# Snyder1_ESP32_V5.net
KiCad netlist of a schematic drawn in EAGLE
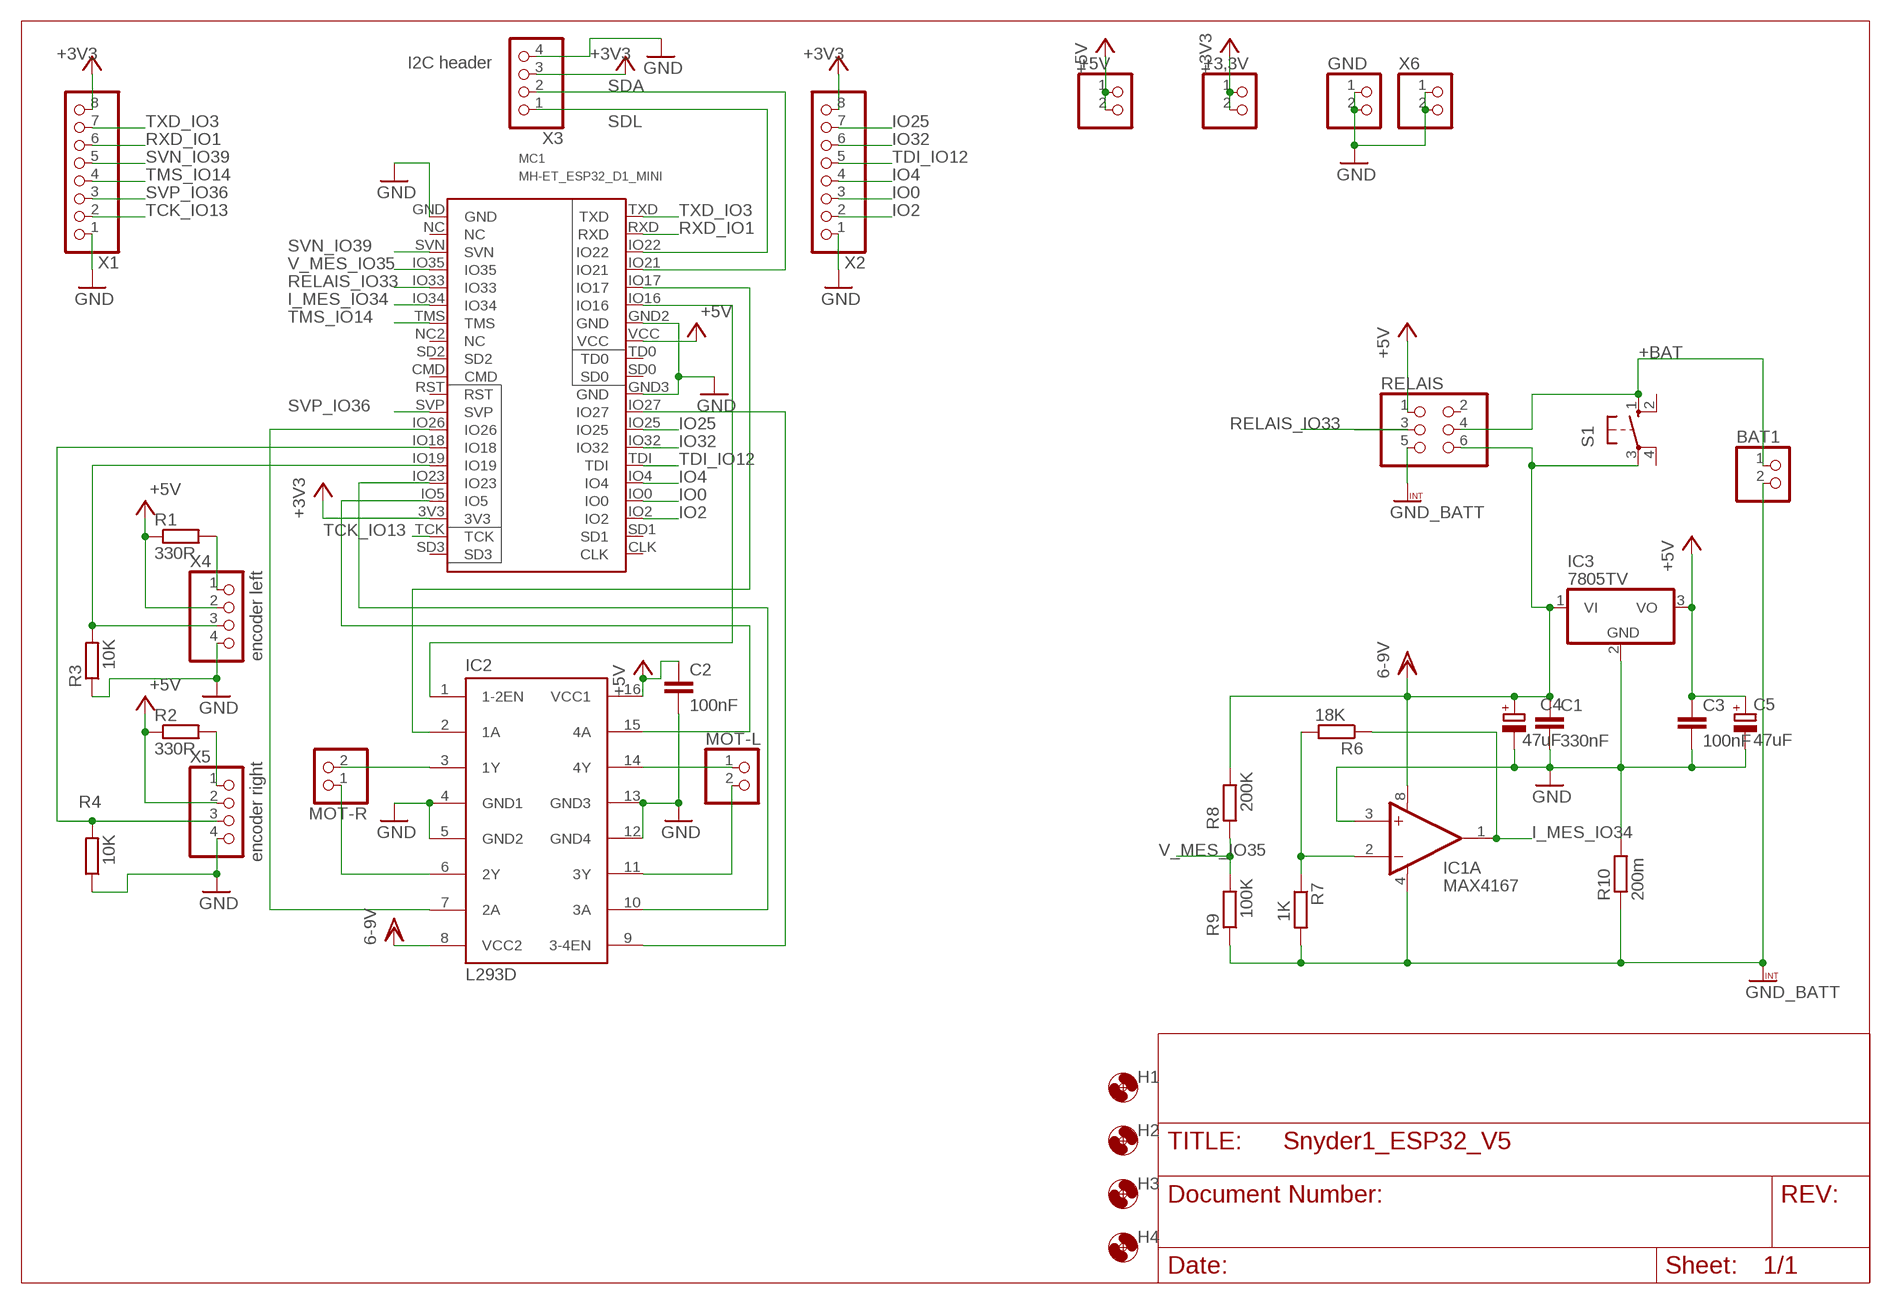
[diagram p0: schematic, sheet 1]

(export (version "E")
  (design (tool "Eeschema 10.0.6"))
  (components
    (comp (ref "+3,3V")
      (value "PINHD-1X2")
      (footprint "eagle-import:1X02")
      (libsource (lib "eagle-import") (part "PINHD-1X2"))
    )
    (comp (ref "+5V")
      (value "PINHD-1X2")
      (footprint "eagle-import:1X02")
      (libsource (lib "eagle-import") (part "PINHD-1X2"))
    )
    (comp (ref "BAT1")
      (value "PINHD-1X2")
      (footprint "eagle-import:1X02")
      (libsource (lib "eagle-import") (part "PINHD-1X2"))
    )
    (comp (ref "C1")
      (value "330nF")
      (footprint "eagle-import:C050-025X075")
      (libsource (lib "eagle-import") (part "C-EU050-025X075"))
    )
    (comp (ref "C2")
      (value "100nF")
      (footprint "eagle-import:C050-025X075")
      (libsource (lib "eagle-import") (part "C-EU050-025X075"))
    )
    (comp (ref "C3")
      (value "100nF")
      (footprint "eagle-import:C050-025X075")
      (libsource (lib "eagle-import") (part "C-EU050-025X075"))
    )
    (comp (ref "C4")
      (value "47uF")
      (footprint "eagle-import:E2,5-5")
      (libsource (lib "eagle-import") (part "CPOL-EUE2.5-5"))
    )
    (comp (ref "C5")
      (value "47uF")
      (footprint "eagle-import:E2,5-5")
      (libsource (lib "eagle-import") (part "CPOL-EUE2.5-5"))
    )
    (comp (ref "GND")
      (value "PINHD-1X2")
      (footprint "eagle-import:1X02")
      (libsource (lib "eagle-import") (part "PINHD-1X2"))
    )
    (comp (ref "H1")
      (value "MOUNT-HOLE3.2")
      (footprint "eagle-import:3,2")
      (libsource (lib "eagle-import") (part "MOUNT-HOLE3.2"))
    )
    (comp (ref "H2")
      (value "MOUNT-HOLE3.2")
      (footprint "eagle-import:3,2")
      (libsource (lib "eagle-import") (part "MOUNT-HOLE3.2"))
    )
    (comp (ref "H3")
      (value "MOUNT-HOLE3.2")
      (footprint "eagle-import:3,2")
      (libsource (lib "eagle-import") (part "MOUNT-HOLE3.2"))
    )
    (comp (ref "H4")
      (value "MOUNT-HOLE3.2")
      (footprint "eagle-import:3,2")
      (libsource (lib "eagle-import") (part "MOUNT-HOLE3.2"))
    )
    (comp (ref "IC1")
      (value "MAX4167")
      (footprint "eagle-import:DIL08")
      (fields (field (name "MPN") "MAX412CPA"))
      (libsource (lib "eagle-import") (part "MAX412CPA"))
    )
    (comp (ref "IC2")
      (value "L293D")
      (footprint "eagle-import:DIL16")
      (libsource (lib "eagle-import") (part "L293D"))
    )
    (comp (ref "IC3")
      (value "7805TV")
      (footprint "eagle-import:TO220V")
      (libsource (lib "eagle-import") (part "78TV05"))
    )
    (comp (ref "MC1")
      (value "MH-ET_ESP32_D1_MINI")
      (footprint "eagle-import:MH-ET_ESP32_D1_MINI")
      (libsource (lib "eagle-import") (part "MH-ET_ESP32_D1_MINI"))
    )
    (comp (ref "MOT-L")
      (value "PINHD-1X2")
      (footprint "eagle-import:1X02")
      (libsource (lib "eagle-import") (part "PINHD-1X2"))
    )
    (comp (ref "MOT-R")
      (value "PINHD-1X2")
      (footprint "eagle-import:1X02")
      (libsource (lib "eagle-import") (part "PINHD-1X2"))
    )
    (comp (ref "R1")
      (value "330R")
      (footprint "eagle-import:0207_10")
      (libsource (lib "eagle-import") (part "R-EU_0207/10"))
    )
    (comp (ref "R2")
      (value "330R")
      (footprint "eagle-import:0207_10")
      (libsource (lib "eagle-import") (part "R-EU_0207/10"))
    )
    (comp (ref "R3")
      (value "10K")
      (footprint "eagle-import:0207_10")
      (libsource (lib "eagle-import") (part "R-EU_0207/10"))
    )
    (comp (ref "R4")
      (value "10K")
      (footprint "eagle-import:0207_10")
      (libsource (lib "eagle-import") (part "R-EU_0207/10"))
    )
    (comp (ref "R6")
      (value "18K")
      (footprint "eagle-import:0207_10")
      (libsource (lib "eagle-import") (part "R-EU_0207/10"))
    )
    (comp (ref "R7")
      (value "1K")
      (footprint "eagle-import:0207_10")
      (libsource (lib "eagle-import") (part "R-EU_0207/10"))
    )
    (comp (ref "R8")
      (value "200K")
      (footprint "eagle-import:0207_10")
      (libsource (lib "eagle-import") (part "R-EU_0207/10"))
    )
    (comp (ref "R9")
      (value "100K")
      (footprint "eagle-import:0207_10")
      (libsource (lib "eagle-import") (part "R-EU_0207/10"))
    )
    (comp (ref "R10")
      (value "200m")
      (footprint "eagle-import:0411_15")
      (libsource (lib "eagle-import") (part "rcl_334_R-EU_0411/15"))
    )
    (comp (ref "RELAIS")
      (value "PINHD-2X3")
      (footprint "eagle-import:2X03")
      (libsource (lib "eagle-import") (part "PINHD-2X3"))
    )
    (comp (ref "S1")
      (value "10-XX")
      (footprint "eagle-import:B3F-10XX")
      (fields (field (name "MPN") "B3F-1000"))
      (libsource (lib "eagle-import") (part "10-XX"))
    )
    (comp (ref "X1")
      (value "PINHD-1X8")
      (footprint "eagle-import:1X08")
      (libsource (lib "eagle-import") (part "PINHD-1X8"))
    )
    (comp (ref "X2")
      (value "PINHD-1X8")
      (footprint "eagle-import:1X08")
      (libsource (lib "eagle-import") (part "PINHD-1X8"))
    )
    (comp (ref "X3")
      (value "I2C header")
      (footprint "eagle-import:1X04")
      (libsource (lib "eagle-import") (part "PINHD-1X4"))
    )
    (comp (ref "X4")
      (value "encoder left")
      (footprint "eagle-import:1X04")
      (libsource (lib "eagle-import") (part "PINHD-1X4"))
    )
    (comp (ref "X5")
      (value "encoder right")
      (footprint "eagle-import:1X04")
      (libsource (lib "eagle-import") (part "PINHD-1X4"))
    )
    (comp (ref "X6")
      (value "PINHD-1X2")
      (footprint "eagle-import:1X02")
      (libsource (lib "eagle-import") (part "PINHD-1X2"))
    )
  )
  (nets
    (net (code "1") (name "+3V3") (class "Default")
      (node (ref "+3,3V") (pin "1") (pinfunction "1_1") (pintype "passive"))
      (node (ref "+3,3V") (pin "2") (pinfunction "2_2") (pintype "passive"))
      (node (ref "MC1") (pin "3V3") (pinfunction "3V3_3V3") (pintype "bidirectional"))
      (node (ref "X1") (pin "8") (pinfunction "8_8") (pintype "passive"))
      (node (ref "X2") (pin "8") (pinfunction "8_8") (pintype "passive"))
      (node (ref "X3") (pin "3") (pinfunction "3_3") (pintype "passive"))
    )
    (net (code "2") (name "+5V") (class "Default")
      (node (ref "+5V") (pin "1") (pinfunction "1_1") (pintype "passive"))
      (node (ref "+5V") (pin "2") (pinfunction "2_2") (pintype "passive"))
      (node (ref "C2") (pin "1") (pinfunction "1_1") (pintype "passive"))
      (node (ref "C3") (pin "1") (pinfunction "1_1") (pintype "passive"))
      (node (ref "C5") (pin "+") (pinfunction "+_+") (pintype "passive"))
      (node (ref "IC2") (pin "16") (pinfunction "VCC1_16") (pintype "power_in"))
      (node (ref "IC3") (pin "3") (pinfunction "VO_3") (pintype "passive"))
      (node (ref "MC1") (pin "VCC") (pinfunction "VCC_VCC") (pintype "bidirectional"))
      (node (ref "R1") (pin "1") (pinfunction "1_1") (pintype "passive"))
      (node (ref "R2") (pin "1") (pinfunction "1_1") (pintype "passive"))
      (node (ref "RELAIS") (pin "1") (pinfunction "1_1") (pintype "passive"))
      (node (ref "X4") (pin "2") (pinfunction "2_2") (pintype "passive"))
      (node (ref "X5") (pin "2") (pinfunction "2_2") (pintype "passive"))
    )
    (net (code "3") (name "/+BAT") (class "Default")
      (node (ref "BAT1") (pin "1") (pinfunction "1_1") (pintype "passive"))
      (node (ref "RELAIS") (pin "4") (pinfunction "4_4") (pintype "passive"))
      (node (ref "S1") (pin "1") (pinfunction "S_1") (pintype "passive"))
    )
    (net (code "4") (name "/IO0") (class "Default")
      (node (ref "MC1") (pin "IO0") (pinfunction "IO0_IO0") (pintype "bidirectional"))
      (node (ref "X2") (pin "3") (pinfunction "3_3") (pintype "passive"))
    )
    (net (code "5") (name "/IO2") (class "Default")
      (node (ref "MC1") (pin "IO2") (pinfunction "IO2_IO2") (pintype "bidirectional"))
      (node (ref "X2") (pin "2") (pinfunction "2_2") (pintype "passive"))
    )
    (net (code "6") (name "/IO4") (class "Default")
      (node (ref "MC1") (pin "IO4") (pinfunction "IO4_IO4") (pintype "bidirectional"))
      (node (ref "X2") (pin "4") (pinfunction "4_4") (pintype "passive"))
    )
    (net (code "7") (name "/IO25") (class "Default")
      (node (ref "MC1") (pin "IO25") (pinfunction "IO25_IO25") (pintype "bidirectional"))
      (node (ref "X2") (pin "7") (pinfunction "7_7") (pintype "passive"))
    )
    (net (code "8") (name "/IO32") (class "Default")
      (node (ref "MC1") (pin "IO32") (pinfunction "IO32_IO32") (pintype "bidirectional"))
      (node (ref "X2") (pin "6") (pinfunction "6_6") (pintype "passive"))
    )
    (net (code "9") (name "/I_MES_IO34") (class "Default")
      (node (ref "IC1") (pin "1") (pinfunction "OUT_1") (pintype "output"))
      (node (ref "MC1") (pin "IO34") (pinfunction "IO34_IO34") (pintype "bidirectional"))
      (node (ref "R6") (pin "1") (pinfunction "1_1") (pintype "passive"))
    )
    (net (code "10") (name "/RELAIS_IO33") (class "Default")
      (node (ref "MC1") (pin "IO33") (pinfunction "IO33_IO33") (pintype "bidirectional"))
      (node (ref "RELAIS") (pin "3") (pinfunction "3_3") (pintype "passive"))
    )
    (net (code "11") (name "/RXD_IO1") (class "Default")
      (node (ref "MC1") (pin "RXD") (pinfunction "RXD_RXD") (pintype "bidirectional"))
      (node (ref "X1") (pin "6") (pinfunction "6_6") (pintype "passive"))
    )
    (net (code "12") (name "/SDA") (class "Default")
      (node (ref "MC1") (pin "IO21") (pinfunction "IO21_IO21") (pintype "bidirectional"))
      (node (ref "X3") (pin "2") (pinfunction "2_2") (pintype "passive"))
    )
    (net (code "13") (name "/SDL") (class "Default")
      (node (ref "MC1") (pin "IO22") (pinfunction "IO22_IO22") (pintype "bidirectional"))
      (node (ref "X3") (pin "1") (pinfunction "1_1") (pintype "passive"))
    )
    (net (code "14") (name "/SVN_IO39") (class "Default")
      (node (ref "MC1") (pin "SVN") (pinfunction "SVN_SVN") (pintype "bidirectional"))
      (node (ref "X1") (pin "5") (pinfunction "5_5") (pintype "passive"))
    )
    (net (code "15") (name "/SVP_IO36") (class "Default")
      (node (ref "MC1") (pin "SVP") (pinfunction "SVP_SVP") (pintype "bidirectional"))
      (node (ref "X1") (pin "3") (pinfunction "3_3") (pintype "passive"))
    )
    (net (code "16") (name "/TCK_IO13") (class "Default")
      (node (ref "MC1") (pin "TCK") (pinfunction "TCK_TCK") (pintype "bidirectional"))
      (node (ref "X1") (pin "2") (pinfunction "2_2") (pintype "passive"))
    )
    (net (code "17") (name "/TDI_IO12") (class "Default")
      (node (ref "MC1") (pin "TDI") (pinfunction "TDI_TDI") (pintype "bidirectional"))
      (node (ref "X2") (pin "5") (pinfunction "5_5") (pintype "passive"))
    )
    (net (code "18") (name "/TMS_IO14") (class "Default")
      (node (ref "MC1") (pin "TMS") (pinfunction "TMS_TMS") (pintype "bidirectional"))
      (node (ref "X1") (pin "4") (pinfunction "4_4") (pintype "passive"))
    )
    (net (code "19") (name "/TXD_IO3") (class "Default")
      (node (ref "MC1") (pin "TXD") (pinfunction "TXD_TXD") (pintype "bidirectional"))
      (node (ref "X1") (pin "7") (pinfunction "7_7") (pintype "passive"))
    )
    (net (code "20") (name "/V_MES_IO35") (class "Default")
      (node (ref "MC1") (pin "IO35") (pinfunction "IO35_IO35") (pintype "bidirectional"))
      (node (ref "R8") (pin "1") (pinfunction "1_1") (pintype "passive"))
      (node (ref "R9") (pin "2") (pinfunction "2_2") (pintype "passive"))
    )
    (net (code "21") (name "6-9V") (class "Default")
      (node (ref "C1") (pin "1") (pinfunction "1_1") (pintype "passive"))
      (node (ref "C4") (pin "+") (pinfunction "+_+") (pintype "passive"))
      (node (ref "IC1") (pin "8") (pinfunction "V+_8") (pintype "power_in"))
      (node (ref "IC2") (pin "8") (pinfunction "VCC2_8") (pintype "power_in"))
      (node (ref "IC3") (pin "1") (pinfunction "VI_1") (pintype "input"))
      (node (ref "R8") (pin "2") (pinfunction "2_2") (pintype "passive"))
      (node (ref "RELAIS") (pin "6") (pinfunction "6_6") (pintype "passive"))
      (node (ref "S1") (pin "3") (pinfunction "P_3") (pintype "passive"))
    )
    (net (code "22") (name "GND") (class "Default")
      (node (ref "C1") (pin "2") (pinfunction "2_2") (pintype "passive"))
      (node (ref "C2") (pin "2") (pinfunction "2_2") (pintype "passive"))
      (node (ref "C3") (pin "2") (pinfunction "2_2") (pintype "passive"))
      (node (ref "C4") (pin "-") (pinfunction "-_-") (pintype "passive"))
      (node (ref "C5") (pin "-") (pinfunction "-_-") (pintype "passive"))
      (node (ref "GND") (pin "1") (pinfunction "1_1") (pintype "passive"))
      (node (ref "GND") (pin "2") (pinfunction "2_2") (pintype "passive"))
      (node (ref "IC1") (pin "3") (pinfunction "+IN_3") (pintype "input"))
      (node (ref "IC2") (pin "12") (pinfunction "GND4_12") (pintype "power_in"))
      (node (ref "IC2") (pin "13") (pinfunction "GND3_13") (pintype "power_in"))
      (node (ref "IC2") (pin "4") (pinfunction "GND1_4") (pintype "power_in"))
      (node (ref "IC2") (pin "5") (pinfunction "GND2_5") (pintype "power_in"))
      (node (ref "IC3") (pin "2") (pinfunction "GND_2") (pintype "passive"))
      (node (ref "MC1") (pin "GND") (pinfunction "GND_GND") (pintype "bidirectional"))
      (node (ref "MC1") (pin "GND2") (pinfunction "GND_GND2") (pintype "bidirectional"))
      (node (ref "MC1") (pin "GND3") (pinfunction "GND_GND3") (pintype "bidirectional"))
      (node (ref "R10") (pin "2") (pinfunction "2_2") (pintype "passive"))
      (node (ref "R3") (pin "1") (pinfunction "1_1") (pintype "passive"))
      (node (ref "R4") (pin "1") (pinfunction "1_1") (pintype "passive"))
      (node (ref "X1") (pin "1") (pinfunction "1_1") (pintype "passive"))
      (node (ref "X2") (pin "1") (pinfunction "1_1") (pintype "passive"))
      (node (ref "X3") (pin "4") (pinfunction "4_4") (pintype "passive"))
      (node (ref "X4") (pin "4") (pinfunction "4_4") (pintype "passive"))
      (node (ref "X5") (pin "4") (pinfunction "4_4") (pintype "passive"))
      (node (ref "X6") (pin "1") (pinfunction "1_1") (pintype "passive"))
      (node (ref "X6") (pin "2") (pinfunction "2_2") (pintype "passive"))
    )
    (net (code "23") (name "GND_BATT") (class "Default")
      (node (ref "BAT1") (pin "2") (pinfunction "2_2") (pintype "passive"))
      (node (ref "IC1") (pin "4") (pinfunction "V-_4") (pintype "power_in"))
      (node (ref "R10") (pin "1") (pinfunction "1_1") (pintype "passive"))
      (node (ref "R7") (pin "2") (pinfunction "2_2") (pintype "passive"))
      (node (ref "R9") (pin "1") (pinfunction "1_1") (pintype "passive"))
      (node (ref "RELAIS") (pin "5") (pinfunction "5_5") (pintype "passive"))
    )
    (net (code "24") (name "Net-(IC1A--IN)") (class "Default")
      (node (ref "IC1") (pin "2") (pinfunction "-IN_2") (pintype "input"))
      (node (ref "R6") (pin "2") (pinfunction "2_2") (pintype "passive"))
      (node (ref "R7") (pin "1") (pinfunction "1_1") (pintype "passive"))
    )
    (net (code "25") (name "Net-(IC2-1-2EN)") (class "Default")
      (node (ref "IC2") (pin "1") (pinfunction "1-2EN_1") (pintype "input"))
      (node (ref "MC1") (pin "IO16") (pinfunction "IO16_IO16") (pintype "bidirectional"))
    )
    (net (code "26") (name "Net-(IC2-1A)") (class "Default")
      (node (ref "IC2") (pin "2") (pinfunction "1A_2") (pintype "input"))
      (node (ref "MC1") (pin "IO17") (pinfunction "IO17_IO17") (pintype "bidirectional"))
    )
    (net (code "27") (name "Net-(IC2-1Y)") (class "Default")
      (node (ref "IC2") (pin "3") (pinfunction "1Y_3") (pintype "output"))
      (node (ref "MOT-R") (pin "2") (pinfunction "2_2") (pintype "passive"))
    )
    (net (code "28") (name "Net-(IC2-2A)") (class "Default")
      (node (ref "IC2") (pin "7") (pinfunction "2A_7") (pintype "input"))
      (node (ref "MC1") (pin "IO26") (pinfunction "IO26_IO26") (pintype "bidirectional"))
    )
    (net (code "29") (name "Net-(IC2-2Y)") (class "Default")
      (node (ref "IC2") (pin "6") (pinfunction "2Y_6") (pintype "output"))
      (node (ref "MOT-R") (pin "1") (pinfunction "1_1") (pintype "passive"))
    )
    (net (code "30") (name "Net-(IC2-3-4EN)") (class "Default")
      (node (ref "IC2") (pin "9") (pinfunction "3-4EN_9") (pintype "input"))
      (node (ref "MC1") (pin "IO27") (pinfunction "IO27_IO27") (pintype "bidirectional"))
    )
    (net (code "31") (name "Net-(IC2-3A)") (class "Default")
      (node (ref "IC2") (pin "10") (pinfunction "3A_10") (pintype "input"))
      (node (ref "MC1") (pin "IO23") (pinfunction "IO23_IO23") (pintype "bidirectional"))
    )
    (net (code "32") (name "Net-(IC2-3Y)") (class "Default")
      (node (ref "IC2") (pin "11") (pinfunction "3Y_11") (pintype "output"))
      (node (ref "MOT-L") (pin "2") (pinfunction "2_2") (pintype "passive"))
    )
    (net (code "33") (name "Net-(IC2-4A)") (class "Default")
      (node (ref "IC2") (pin "15") (pinfunction "4A_15") (pintype "input"))
      (node (ref "MC1") (pin "IO5") (pinfunction "IO5_IO5") (pintype "bidirectional"))
    )
    (net (code "34") (name "Net-(IC2-4Y)") (class "Default")
      (node (ref "IC2") (pin "14") (pinfunction "4Y_14") (pintype "output"))
      (node (ref "MOT-L") (pin "1") (pinfunction "1_1") (pintype "passive"))
    )
    (net (code "35") (name "Net-(MC1-PadIO18)") (class "Default")
      (node (ref "MC1") (pin "IO18") (pinfunction "IO18_IO18") (pintype "bidirectional"))
      (node (ref "R4") (pin "2") (pinfunction "2_2") (pintype "passive"))
      (node (ref "X5") (pin "3") (pinfunction "3_3") (pintype "passive"))
    )
    (net (code "36") (name "Net-(MC1-PadIO19)") (class "Default")
      (node (ref "MC1") (pin "IO19") (pinfunction "IO19_IO19") (pintype "bidirectional"))
      (node (ref "R3") (pin "2") (pinfunction "2_2") (pintype "passive"))
      (node (ref "X4") (pin "3") (pinfunction "3_3") (pintype "passive"))
    )
    (net (code "37") (name "Net-(R1-Pad2)") (class "Default")
      (node (ref "R1") (pin "2") (pinfunction "2_2") (pintype "passive"))
      (node (ref "X4") (pin "1") (pinfunction "1_1") (pintype "passive"))
    )
    (net (code "38") (name "Net-(R2-Pad2)") (class "Default")
      (node (ref "R2") (pin "2") (pinfunction "2_2") (pintype "passive"))
      (node (ref "X5") (pin "1") (pinfunction "1_1") (pintype "passive"))
    )
    (net (code "39") (name "unconnected-(MC1-NC-PadNC2)") (class "Default")
      (node (ref "MC1") (pin "NC2") (pinfunction "NC_NC2") (pintype "bidirectional"))
    )
    (net (code "40") (name "unconnected-(MC1-PadCLK)") (class "Default")
      (node (ref "MC1") (pin "CLK") (pinfunction "CLK_CLK") (pintype "bidirectional"))
    )
    (net (code "41") (name "unconnected-(MC1-PadCMD)") (class "Default")
      (node (ref "MC1") (pin "CMD") (pinfunction "CMD_CMD") (pintype "bidirectional"))
    )
    (net (code "42") (name "unconnected-(MC1-PadNC)") (class "Default")
      (node (ref "MC1") (pin "NC") (pinfunction "NC_NC") (pintype "bidirectional"))
    )
    (net (code "43") (name "unconnected-(MC1-PadRST)") (class "Default")
      (node (ref "MC1") (pin "RST") (pinfunction "RST_RST") (pintype "bidirectional"))
    )
    (net (code "44") (name "unconnected-(MC1-PadSD0)") (class "Default")
      (node (ref "MC1") (pin "SD0") (pinfunction "SD0_SD0") (pintype "bidirectional"))
    )
    (net (code "45") (name "unconnected-(MC1-PadSD1)") (class "Default")
      (node (ref "MC1") (pin "SD1") (pinfunction "SD1_SD1") (pintype "bidirectional"))
    )
    (net (code "46") (name "unconnected-(MC1-PadSD2)") (class "Default")
      (node (ref "MC1") (pin "SD2") (pinfunction "SD2_SD2") (pintype "bidirectional"))
    )
    (net (code "47") (name "unconnected-(MC1-PadSD3)") (class "Default")
      (node (ref "MC1") (pin "SD3") (pinfunction "SD3_SD3") (pintype "bidirectional"))
    )
    (net (code "48") (name "unconnected-(MC1-PadTD0)") (class "Default")
      (node (ref "MC1") (pin "TD0") (pinfunction "TD0_TD0") (pintype "bidirectional"))
    )
    (net (code "49") (name "unconnected-(RELAIS-Pad2)") (class "Default")
      (node (ref "RELAIS") (pin "2") (pinfunction "2_2") (pintype "passive"))
    )
    (net (code "50") (name "unconnected-(S1-P1-Pad4)") (class "Default")
      (node (ref "S1") (pin "4") (pinfunction "P1_4") (pintype "passive"))
    )
    (net (code "51") (name "unconnected-(S1-S1-Pad2)") (class "Default")
      (node (ref "S1") (pin "2") (pinfunction "S1_2") (pintype "passive"))
    )
  )
)
